# StackBreakoutConnection_4layers_V1_0_wit.net
KiCad netlist of a schematic drawn in EAGLE
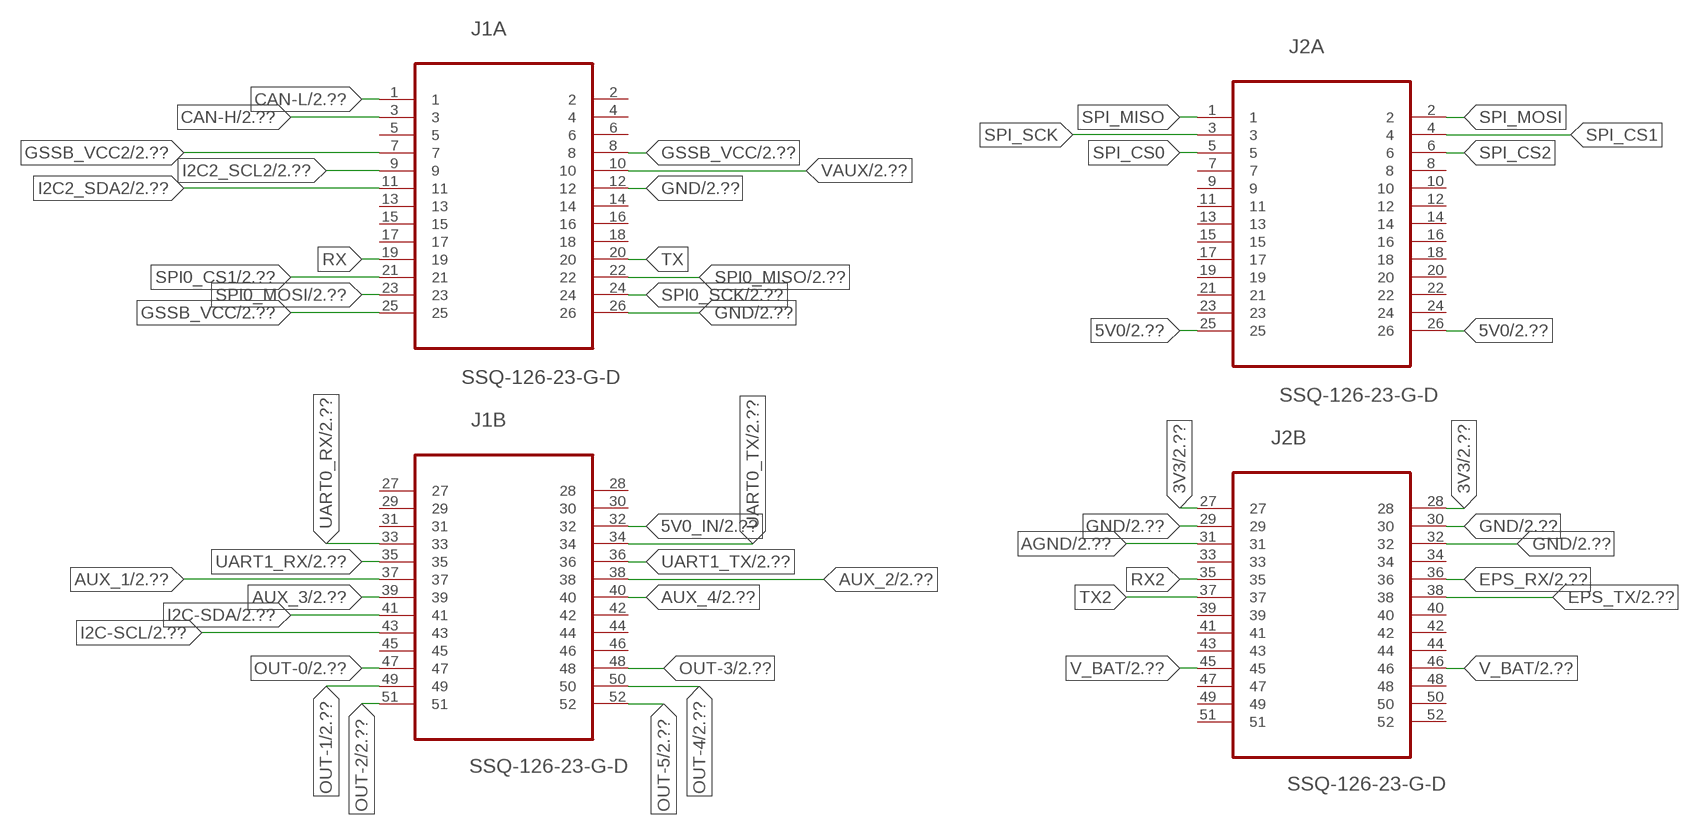
[diagram p0: schematic, sheet 1]
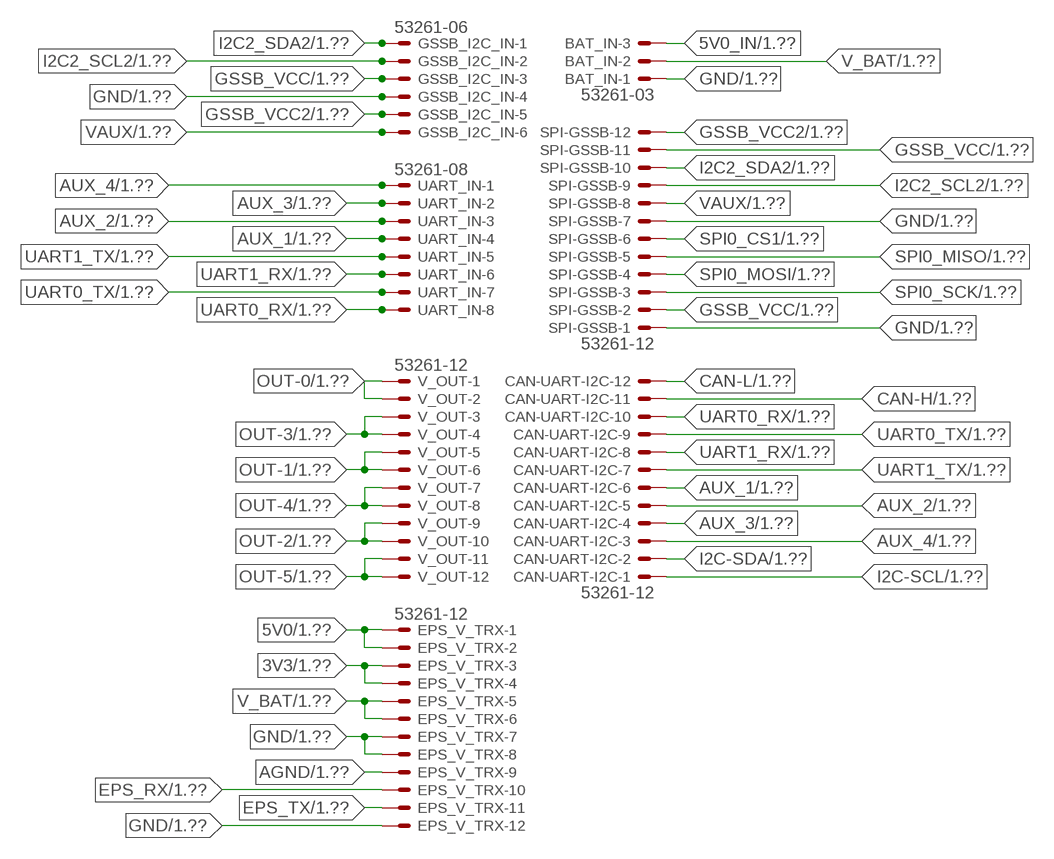
[diagram p1: schematic, sheet 2]

(export (version "E")
  (design (tool "Eeschema 10.0.6"))
  (components
    (comp (ref "J1")
      (value "SSQ-126-23-G-D")
      (footprint "eagle-import:SAMTEC_SSQ-126-23-G-D")
      (libsource (lib "eagle-import") (part "SSQ-126-23-G-D"))
    )
    (comp (ref "J2")
      (value "SSQ-126-23-G-D")
      (footprint "eagle-import:SAMTEC_SSQ-126-23-G-D")
      (libsource (lib "eagle-import") (part "SSQ-126-23-G-D"))
    )
    (comp (ref "BAT_IN")
      (value "53261-03")
      (footprint "eagle-import:53261-03")
      (fields (field (name "MF") "MOLEX") (field (name "MPN") "53261-0390"))
      (libsource (lib "eagle-import") (part "53?-03261"))
    )
    (comp (ref "CAN-UART-I2C")
      (value "53261-12")
      (footprint "eagle-import:53261-12")
      (fields (field (name "MF") "MOLEX") (field (name "MPN") "53261-1271"))
      (libsource (lib "eagle-import") (part "53?-12261"))
    )
    (comp (ref "EPS_V_TRX")
      (value "53261-12")
      (footprint "eagle-import:53261-12")
      (fields (field (name "MF") "MOLEX") (field (name "MPN") "53261-1271"))
      (libsource (lib "eagle-import") (part "53?-12261"))
    )
    (comp (ref "GSSB_I2C_IN")
      (value "53261-06")
      (footprint "eagle-import:53261-06")
      (fields (field (name "MF") "MOLEX"))
      (libsource (lib "eagle-import") (part "53?-06261"))
    )
    (comp (ref "SPI-GSSB")
      (value "53261-12")
      (footprint "eagle-import:53261-12")
      (fields (field (name "MF") "MOLEX") (field (name "MPN") "53261-1271"))
      (libsource (lib "eagle-import") (part "53?-12261"))
    )
    (comp (ref "UART_IN")
      (value "53261-08")
      (footprint "eagle-import:53261-08")
      (fields (field (name "MF") "MOLEX"))
      (libsource (lib "eagle-import") (part "53?-08261"))
    )
    (comp (ref "V_OUT")
      (value "53261-12")
      (footprint "eagle-import:53261-12")
      (fields (field (name "MF") "MOLEX") (field (name "MPN") "53261-1271"))
      (libsource (lib "eagle-import") (part "53?-12261"))
    )
  )
  (nets
    (net (code "1") (name "3V3") (class "Default")
      (node (ref "EPS_V_TRX") (pin "3") (pinfunction "S_3") (pintype "passive"))
      (node (ref "EPS_V_TRX") (pin "4") (pinfunction "S_4") (pintype "passive"))
      (node (ref "J2") (pin "27") (pinfunction "27_27") (pintype "passive"))
      (node (ref "J2") (pin "28") (pinfunction "28_28") (pintype "passive"))
    )
    (net (code "2") (name "5V0") (class "Default")
      (node (ref "EPS_V_TRX") (pin "1") (pinfunction "S_1") (pintype "passive"))
      (node (ref "EPS_V_TRX") (pin "2") (pinfunction "S_2") (pintype "passive"))
      (node (ref "J2") (pin "25") (pinfunction "25_25") (pintype "passive"))
      (node (ref "J2") (pin "26") (pinfunction "26_26") (pintype "passive"))
    )
    (net (code "3") (name "5V0_IN") (class "Default")
      (node (ref "BAT_IN") (pin "3") (pinfunction "S_3") (pintype "passive"))
      (node (ref "J1") (pin "32") (pinfunction "32_32") (pintype "passive"))
    )
    (net (code "4") (name "AGND") (class "Default")
      (node (ref "EPS_V_TRX") (pin "9") (pinfunction "S_9") (pintype "passive"))
      (node (ref "J2") (pin "31") (pinfunction "31_31") (pintype "passive"))
    )
    (net (code "5") (name "AUX_1") (class "Default")
      (node (ref "CAN-UART-I2C") (pin "6") (pinfunction "S_6") (pintype "passive"))
      (node (ref "J1") (pin "37") (pinfunction "37_37") (pintype "passive"))
      (node (ref "UART_IN") (pin "4") (pinfunction "S_4") (pintype "passive"))
    )
    (net (code "6") (name "AUX_2") (class "Default")
      (node (ref "CAN-UART-I2C") (pin "5") (pinfunction "S_5") (pintype "passive"))
      (node (ref "J1") (pin "38") (pinfunction "38_38") (pintype "passive"))
      (node (ref "UART_IN") (pin "3") (pinfunction "S_3") (pintype "passive"))
    )
    (net (code "7") (name "AUX_3") (class "Default")
      (node (ref "CAN-UART-I2C") (pin "4") (pinfunction "S_4") (pintype "passive"))
      (node (ref "J1") (pin "39") (pinfunction "39_39") (pintype "passive"))
      (node (ref "UART_IN") (pin "2") (pinfunction "S_2") (pintype "passive"))
    )
    (net (code "8") (name "AUX_4") (class "Default")
      (node (ref "CAN-UART-I2C") (pin "3") (pinfunction "S_3") (pintype "passive"))
      (node (ref "J1") (pin "40") (pinfunction "40_40") (pintype "passive"))
      (node (ref "UART_IN") (pin "1") (pinfunction "S_1") (pintype "passive"))
    )
    (net (code "9") (name "CAN-H") (class "Default")
      (node (ref "CAN-UART-I2C") (pin "11") (pinfunction "S_11") (pintype "passive"))
      (node (ref "J1") (pin "3") (pinfunction "3_3") (pintype "passive"))
    )
    (net (code "10") (name "CAN-L") (class "Default")
      (node (ref "CAN-UART-I2C") (pin "12") (pinfunction "S_12") (pintype "passive"))
      (node (ref "J1") (pin "1") (pinfunction "1_1") (pintype "passive"))
    )
    (net (code "11") (name "EPS_RX") (class "Default")
      (node (ref "EPS_V_TRX") (pin "10") (pinfunction "S_10") (pintype "passive"))
      (node (ref "J2") (pin "36") (pinfunction "36_36") (pintype "passive"))
    )
    (net (code "12") (name "EPS_TX") (class "Default")
      (node (ref "EPS_V_TRX") (pin "11") (pinfunction "S_11") (pintype "passive"))
      (node (ref "J2") (pin "38") (pinfunction "38_38") (pintype "passive"))
    )
    (net (code "13") (name "GND") (class "Default")
      (node (ref "BAT_IN") (pin "1") (pinfunction "S_1") (pintype "passive"))
      (node (ref "EPS_V_TRX") (pin "12") (pinfunction "S_12") (pintype "passive"))
      (node (ref "EPS_V_TRX") (pin "7") (pinfunction "S_7") (pintype "passive"))
      (node (ref "EPS_V_TRX") (pin "8") (pinfunction "S_8") (pintype "passive"))
      (node (ref "GSSB_I2C_IN") (pin "4") (pinfunction "S_4") (pintype "passive"))
      (node (ref "J1") (pin "12") (pinfunction "12_12") (pintype "passive"))
      (node (ref "J1") (pin "26") (pinfunction "26_26") (pintype "passive"))
      (node (ref "J2") (pin "29") (pinfunction "29_29") (pintype "passive"))
      (node (ref "J2") (pin "30") (pinfunction "30_30") (pintype "passive"))
      (node (ref "J2") (pin "32") (pinfunction "32_32") (pintype "passive"))
      (node (ref "SPI-GSSB") (pin "1") (pinfunction "S_1") (pintype "passive"))
      (node (ref "SPI-GSSB") (pin "7") (pinfunction "S_7") (pintype "passive"))
    )
    (net (code "14") (name "GSSB_VCC") (class "Default")
      (node (ref "GSSB_I2C_IN") (pin "3") (pinfunction "S_3") (pintype "passive"))
      (node (ref "J1") (pin "25") (pinfunction "25_25") (pintype "passive"))
      (node (ref "J1") (pin "8") (pinfunction "8_8") (pintype "passive"))
      (node (ref "SPI-GSSB") (pin "11") (pinfunction "S_11") (pintype "passive"))
      (node (ref "SPI-GSSB") (pin "2") (pinfunction "S_2") (pintype "passive"))
    )
    (net (code "15") (name "GSSB_VCC2") (class "Default")
      (node (ref "GSSB_I2C_IN") (pin "5") (pinfunction "S_5") (pintype "passive"))
      (node (ref "J1") (pin "7") (pinfunction "7_7") (pintype "passive"))
      (node (ref "SPI-GSSB") (pin "12") (pinfunction "S_12") (pintype "passive"))
    )
    (net (code "16") (name "I2C-SCL") (class "Default")
      (node (ref "CAN-UART-I2C") (pin "1") (pinfunction "S_1") (pintype "passive"))
      (node (ref "J1") (pin "43") (pinfunction "43_43") (pintype "passive"))
    )
    (net (code "17") (name "I2C-SDA") (class "Default")
      (node (ref "CAN-UART-I2C") (pin "2") (pinfunction "S_2") (pintype "passive"))
      (node (ref "J1") (pin "41") (pinfunction "41_41") (pintype "passive"))
    )
    (net (code "18") (name "I2C2_SCL2") (class "Default")
      (node (ref "GSSB_I2C_IN") (pin "2") (pinfunction "S_2") (pintype "passive"))
      (node (ref "J1") (pin "9") (pinfunction "9_9") (pintype "passive"))
      (node (ref "SPI-GSSB") (pin "9") (pinfunction "S_9") (pintype "passive"))
    )
    (net (code "19") (name "I2C2_SDA2") (class "Default")
      (node (ref "GSSB_I2C_IN") (pin "1") (pinfunction "S_1") (pintype "passive"))
      (node (ref "J1") (pin "11") (pinfunction "11_11") (pintype "passive"))
      (node (ref "SPI-GSSB") (pin "10") (pinfunction "S_10") (pintype "passive"))
    )
    (net (code "20") (name "OUT-0") (class "Default")
      (node (ref "J1") (pin "47") (pinfunction "47_47") (pintype "passive"))
      (node (ref "V_OUT") (pin "1") (pinfunction "S_1") (pintype "passive"))
      (node (ref "V_OUT") (pin "2") (pinfunction "S_2") (pintype "passive"))
    )
    (net (code "21") (name "OUT-1") (class "Default")
      (node (ref "J1") (pin "49") (pinfunction "49_49") (pintype "passive"))
      (node (ref "V_OUT") (pin "5") (pinfunction "S_5") (pintype "passive"))
      (node (ref "V_OUT") (pin "6") (pinfunction "S_6") (pintype "passive"))
    )
    (net (code "22") (name "OUT-2") (class "Default")
      (node (ref "J1") (pin "51") (pinfunction "51_51") (pintype "passive"))
      (node (ref "V_OUT") (pin "10") (pinfunction "S_10") (pintype "passive"))
      (node (ref "V_OUT") (pin "9") (pinfunction "S_9") (pintype "passive"))
    )
    (net (code "23") (name "OUT-3") (class "Default")
      (node (ref "J1") (pin "48") (pinfunction "48_48") (pintype "passive"))
      (node (ref "V_OUT") (pin "3") (pinfunction "S_3") (pintype "passive"))
      (node (ref "V_OUT") (pin "4") (pinfunction "S_4") (pintype "passive"))
    )
    (net (code "24") (name "OUT-4") (class "Default")
      (node (ref "J1") (pin "50") (pinfunction "50_50") (pintype "passive"))
      (node (ref "V_OUT") (pin "7") (pinfunction "S_7") (pintype "passive"))
      (node (ref "V_OUT") (pin "8") (pinfunction "S_8") (pintype "passive"))
    )
    (net (code "25") (name "OUT-5") (class "Default")
      (node (ref "J1") (pin "52") (pinfunction "52_52") (pintype "passive"))
      (node (ref "V_OUT") (pin "11") (pinfunction "S_11") (pintype "passive"))
      (node (ref "V_OUT") (pin "12") (pinfunction "S_12") (pintype "passive"))
    )
    (net (code "26") (name "RX") (class "Default")
      (node (ref "J1") (pin "19") (pinfunction "19_19") (pintype "passive"))
    )
    (net (code "27") (name "RX2") (class "Default")
      (node (ref "J2") (pin "35") (pinfunction "35_35") (pintype "passive"))
    )
    (net (code "28") (name "SPI0_CS1") (class "Default")
      (node (ref "J1") (pin "21") (pinfunction "21_21") (pintype "passive"))
      (node (ref "SPI-GSSB") (pin "6") (pinfunction "S_6") (pintype "passive"))
    )
    (net (code "29") (name "SPI0_MISO") (class "Default")
      (node (ref "J1") (pin "22") (pinfunction "22_22") (pintype "passive"))
      (node (ref "SPI-GSSB") (pin "5") (pinfunction "S_5") (pintype "passive"))
    )
    (net (code "30") (name "SPI0_MOSI") (class "Default")
      (node (ref "J1") (pin "23") (pinfunction "23_23") (pintype "passive"))
      (node (ref "SPI-GSSB") (pin "4") (pinfunction "S_4") (pintype "passive"))
    )
    (net (code "31") (name "SPI0_SCK") (class "Default")
      (node (ref "J1") (pin "24") (pinfunction "24_24") (pintype "passive"))
      (node (ref "SPI-GSSB") (pin "3") (pinfunction "S_3") (pintype "passive"))
    )
    (net (code "32") (name "SPI_CS0") (class "Default")
      (node (ref "J2") (pin "5") (pinfunction "5_5") (pintype "passive"))
    )
    (net (code "33") (name "SPI_CS1") (class "Default")
      (node (ref "J2") (pin "4") (pinfunction "4_4") (pintype "passive"))
    )
    (net (code "34") (name "SPI_CS2") (class "Default")
      (node (ref "J2") (pin "6") (pinfunction "6_6") (pintype "passive"))
    )
    (net (code "35") (name "SPI_MISO") (class "Default")
      (node (ref "J2") (pin "1") (pinfunction "1_1") (pintype "passive"))
    )
    (net (code "36") (name "SPI_MOSI") (class "Default")
      (node (ref "J2") (pin "2") (pinfunction "2_2") (pintype "passive"))
    )
    (net (code "37") (name "SPI_SCK") (class "Default")
      (node (ref "J2") (pin "3") (pinfunction "3_3") (pintype "passive"))
    )
    (net (code "38") (name "TX") (class "Default")
      (node (ref "J1") (pin "20") (pinfunction "20_20") (pintype "passive"))
    )
    (net (code "39") (name "TX2") (class "Default")
      (node (ref "J2") (pin "37") (pinfunction "37_37") (pintype "passive"))
    )
    (net (code "40") (name "UART0_RX") (class "Default")
      (node (ref "CAN-UART-I2C") (pin "10") (pinfunction "S_10") (pintype "passive"))
      (node (ref "J1") (pin "33") (pinfunction "33_33") (pintype "passive"))
      (node (ref "UART_IN") (pin "8") (pinfunction "S_8") (pintype "passive"))
    )
    (net (code "41") (name "UART0_TX") (class "Default")
      (node (ref "CAN-UART-I2C") (pin "9") (pinfunction "S_9") (pintype "passive"))
      (node (ref "J1") (pin "34") (pinfunction "34_34") (pintype "passive"))
      (node (ref "UART_IN") (pin "7") (pinfunction "S_7") (pintype "passive"))
    )
    (net (code "42") (name "UART1_RX") (class "Default")
      (node (ref "CAN-UART-I2C") (pin "8") (pinfunction "S_8") (pintype "passive"))
      (node (ref "J1") (pin "35") (pinfunction "35_35") (pintype "passive"))
      (node (ref "UART_IN") (pin "6") (pinfunction "S_6") (pintype "passive"))
    )
    (net (code "43") (name "UART1_TX") (class "Default")
      (node (ref "CAN-UART-I2C") (pin "7") (pinfunction "S_7") (pintype "passive"))
      (node (ref "J1") (pin "36") (pinfunction "36_36") (pintype "passive"))
      (node (ref "UART_IN") (pin "5") (pinfunction "S_5") (pintype "passive"))
    )
    (net (code "44") (name "VAUX") (class "Default")
      (node (ref "GSSB_I2C_IN") (pin "6") (pinfunction "S_6") (pintype "passive"))
      (node (ref "J1") (pin "10") (pinfunction "10_10") (pintype "passive"))
      (node (ref "SPI-GSSB") (pin "8") (pinfunction "S_8") (pintype "passive"))
    )
    (net (code "45") (name "V_BAT") (class "Default")
      (node (ref "BAT_IN") (pin "2") (pinfunction "S_2") (pintype "passive"))
      (node (ref "EPS_V_TRX") (pin "5") (pinfunction "S_5") (pintype "passive"))
      (node (ref "EPS_V_TRX") (pin "6") (pinfunction "S_6") (pintype "passive"))
      (node (ref "J2") (pin "45") (pinfunction "45_45") (pintype "passive"))
      (node (ref "J2") (pin "46") (pinfunction "46_46") (pintype "passive"))
    )
    (net (code "46") (name "unconnected-(J1-Pad2)") (class "Default")
      (node (ref "J1") (pin "2") (pinfunction "2_2") (pintype "passive"))
    )
    (net (code "47") (name "unconnected-(J1-Pad4)") (class "Default")
      (node (ref "J1") (pin "4") (pinfunction "4_4") (pintype "passive"))
    )
    (net (code "48") (name "unconnected-(J1-Pad5)") (class "Default")
      (node (ref "J1") (pin "5") (pinfunction "5_5") (pintype "passive"))
    )
    (net (code "49") (name "unconnected-(J1-Pad6)") (class "Default")
      (node (ref "J1") (pin "6") (pinfunction "6_6") (pintype "passive"))
    )
    (net (code "50") (name "unconnected-(J1-Pad13)") (class "Default")
      (node (ref "J1") (pin "13") (pinfunction "13_13") (pintype "passive"))
    )
    (net (code "51") (name "unconnected-(J1-Pad14)") (class "Default")
      (node (ref "J1") (pin "14") (pinfunction "14_14") (pintype "passive"))
    )
    (net (code "52") (name "unconnected-(J1-Pad15)") (class "Default")
      (node (ref "J1") (pin "15") (pinfunction "15_15") (pintype "passive"))
    )
    (net (code "53") (name "unconnected-(J1-Pad16)") (class "Default")
      (node (ref "J1") (pin "16") (pinfunction "16_16") (pintype "passive"))
    )
    (net (code "54") (name "unconnected-(J1-Pad17)") (class "Default")
      (node (ref "J1") (pin "17") (pinfunction "17_17") (pintype "passive"))
    )
    (net (code "55") (name "unconnected-(J1-Pad18)") (class "Default")
      (node (ref "J1") (pin "18") (pinfunction "18_18") (pintype "passive"))
    )
    (net (code "56") (name "unconnected-(J1-Pad27)") (class "Default")
      (node (ref "J1") (pin "27") (pinfunction "27_27") (pintype "passive"))
    )
    (net (code "57") (name "unconnected-(J1-Pad28)") (class "Default")
      (node (ref "J1") (pin "28") (pinfunction "28_28") (pintype "passive"))
    )
    (net (code "58") (name "unconnected-(J1-Pad29)") (class "Default")
      (node (ref "J1") (pin "29") (pinfunction "29_29") (pintype "passive"))
    )
    (net (code "59") (name "unconnected-(J1-Pad30)") (class "Default")
      (node (ref "J1") (pin "30") (pinfunction "30_30") (pintype "passive"))
    )
    (net (code "60") (name "unconnected-(J1-Pad31)") (class "Default")
      (node (ref "J1") (pin "31") (pinfunction "31_31") (pintype "passive"))
    )
    (net (code "61") (name "unconnected-(J1-Pad42)") (class "Default")
      (node (ref "J1") (pin "42") (pinfunction "42_42") (pintype "passive"))
    )
    (net (code "62") (name "unconnected-(J1-Pad44)") (class "Default")
      (node (ref "J1") (pin "44") (pinfunction "44_44") (pintype "passive"))
    )
    (net (code "63") (name "unconnected-(J1-Pad45)") (class "Default")
      (node (ref "J1") (pin "45") (pinfunction "45_45") (pintype "passive"))
    )
    (net (code "64") (name "unconnected-(J1-Pad46)") (class "Default")
      (node (ref "J1") (pin "46") (pinfunction "46_46") (pintype "passive"))
    )
    (net (code "65") (name "unconnected-(J2-Pad7)") (class "Default")
      (node (ref "J2") (pin "7") (pinfunction "7_7") (pintype "passive"))
    )
    (net (code "66") (name "unconnected-(J2-Pad8)") (class "Default")
      (node (ref "J2") (pin "8") (pinfunction "8_8") (pintype "passive"))
    )
    (net (code "67") (name "unconnected-(J2-Pad9)") (class "Default")
      (node (ref "J2") (pin "9") (pinfunction "9_9") (pintype "passive"))
    )
    (net (code "68") (name "unconnected-(J2-Pad10)") (class "Default")
      (node (ref "J2") (pin "10") (pinfunction "10_10") (pintype "passive"))
    )
    (net (code "69") (name "unconnected-(J2-Pad11)") (class "Default")
      (node (ref "J2") (pin "11") (pinfunction "11_11") (pintype "passive"))
    )
    (net (code "70") (name "unconnected-(J2-Pad12)") (class "Default")
      (node (ref "J2") (pin "12") (pinfunction "12_12") (pintype "passive"))
    )
    (net (code "71") (name "unconnected-(J2-Pad13)") (class "Default")
      (node (ref "J2") (pin "13") (pinfunction "13_13") (pintype "passive"))
    )
    (net (code "72") (name "unconnected-(J2-Pad14)") (class "Default")
      (node (ref "J2") (pin "14") (pinfunction "14_14") (pintype "passive"))
    )
    (net (code "73") (name "unconnected-(J2-Pad15)") (class "Default")
      (node (ref "J2") (pin "15") (pinfunction "15_15") (pintype "passive"))
    )
    (net (code "74") (name "unconnected-(J2-Pad16)") (class "Default")
      (node (ref "J2") (pin "16") (pinfunction "16_16") (pintype "passive"))
    )
    (net (code "75") (name "unconnected-(J2-Pad17)") (class "Default")
      (node (ref "J2") (pin "17") (pinfunction "17_17") (pintype "passive"))
    )
    (net (code "76") (name "unconnected-(J2-Pad18)") (class "Default")
      (node (ref "J2") (pin "18") (pinfunction "18_18") (pintype "passive"))
    )
    (net (code "77") (name "unconnected-(J2-Pad19)") (class "Default")
      (node (ref "J2") (pin "19") (pinfunction "19_19") (pintype "passive"))
    )
    (net (code "78") (name "unconnected-(J2-Pad20)") (class "Default")
      (node (ref "J2") (pin "20") (pinfunction "20_20") (pintype "passive"))
    )
    (net (code "79") (name "unconnected-(J2-Pad21)") (class "Default")
      (node (ref "J2") (pin "21") (pinfunction "21_21") (pintype "passive"))
    )
    (net (code "80") (name "unconnected-(J2-Pad22)") (class "Default")
      (node (ref "J2") (pin "22") (pinfunction "22_22") (pintype "passive"))
    )
    (net (code "81") (name "unconnected-(J2-Pad23)") (class "Default")
      (node (ref "J2") (pin "23") (pinfunction "23_23") (pintype "passive"))
    )
    (net (code "82") (name "unconnected-(J2-Pad24)") (class "Default")
      (node (ref "J2") (pin "24") (pinfunction "24_24") (pintype "passive"))
    )
    (net (code "83") (name "unconnected-(J2-Pad33)") (class "Default")
      (node (ref "J2") (pin "33") (pinfunction "33_33") (pintype "passive"))
    )
    (net (code "84") (name "unconnected-(J2-Pad34)") (class "Default")
      (node (ref "J2") (pin "34") (pinfunction "34_34") (pintype "passive"))
    )
    (net (code "85") (name "unconnected-(J2-Pad39)") (class "Default")
      (node (ref "J2") (pin "39") (pinfunction "39_39") (pintype "passive"))
    )
    (net (code "86") (name "unconnected-(J2-Pad40)") (class "Default")
      (node (ref "J2") (pin "40") (pinfunction "40_40") (pintype "passive"))
    )
    (net (code "87") (name "unconnected-(J2-Pad41)") (class "Default")
      (node (ref "J2") (pin "41") (pinfunction "41_41") (pintype "passive"))
    )
    (net (code "88") (name "unconnected-(J2-Pad42)") (class "Default")
      (node (ref "J2") (pin "42") (pinfunction "42_42") (pintype "passive"))
    )
    (net (code "89") (name "unconnected-(J2-Pad43)") (class "Default")
      (node (ref "J2") (pin "43") (pinfunction "43_43") (pintype "passive"))
    )
    (net (code "90") (name "unconnected-(J2-Pad44)") (class "Default")
      (node (ref "J2") (pin "44") (pinfunction "44_44") (pintype "passive"))
    )
    (net (code "91") (name "unconnected-(J2-Pad47)") (class "Default")
      (node (ref "J2") (pin "47") (pinfunction "47_47") (pintype "passive"))
    )
    (net (code "92") (name "unconnected-(J2-Pad48)") (class "Default")
      (node (ref "J2") (pin "48") (pinfunction "48_48") (pintype "passive"))
    )
    (net (code "93") (name "unconnected-(J2-Pad49)") (class "Default")
      (node (ref "J2") (pin "49") (pinfunction "49_49") (pintype "passive"))
    )
    (net (code "94") (name "unconnected-(J2-Pad50)") (class "Default")
      (node (ref "J2") (pin "50") (pinfunction "50_50") (pintype "passive"))
    )
    (net (code "95") (name "unconnected-(J2-Pad51)") (class "Default")
      (node (ref "J2") (pin "51") (pinfunction "51_51") (pintype "passive"))
    )
    (net (code "96") (name "unconnected-(J2-Pad52)") (class "Default")
      (node (ref "J2") (pin "52") (pinfunction "52_52") (pintype "passive"))
    )
  )
)
